# controller_peripherals.net
KiCad netlist of a schematic drawn in Altium Designer
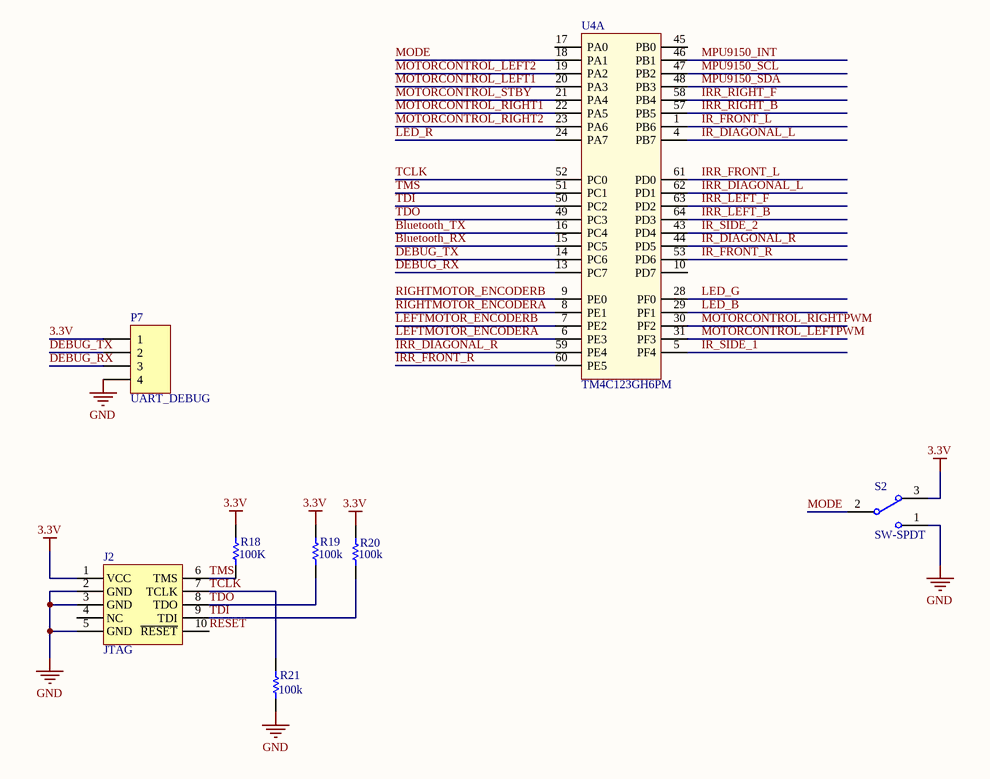
[diagram p0: controller_peripherals.SchDoc]

(export (version "E")
  (design (tool "Eeschema 10.0.6"))
  (components
    (comp (ref "J2")
      (value "JTAG")
      (footprint "HDR2X5")
      (description "10-Pin JTAG Connector for Cortex M4 etc.")
      (libsource (lib "connectors") (part "10-Pin JTAG ARM"))
    )
    (comp (ref "P7")
      (value "UART_DEBUG")
      (footprint "HDR1X4")
      (description "Header, 4-Pin")
      (fields (field (name "PUBLISHER") "Altium Limited"))
      (libsource (lib "Miscellaneous Connectors") (part "Header 4"))
    )
    (comp (ref "R18")
      (value "100K")
      (footprint "0603")
      (description "Resistor")
      (fields (field (name "PUBLISHER") "Altium Limited"))
      (libsource (lib "passives") (part "Resistor"))
    )
    (comp (ref "R19")
      (value "100k")
      (footprint "0603")
      (description "Resistor")
      (fields (field (name "PUBLISHER") "Altium Limited"))
      (libsource (lib "passives") (part "Resistor"))
    )
    (comp (ref "R20")
      (value "100k")
      (footprint "0603")
      (description "Resistor")
      (fields (field (name "PUBLISHER") "Altium Limited"))
      (libsource (lib "passives") (part "Resistor"))
    )
    (comp (ref "R21")
      (value "100k")
      (footprint "0603")
      (description "Resistor")
      (fields (field (name "PUBLISHER") "Altium Limited"))
      (libsource (lib "passives") (part "Resistor"))
    )
    (comp (ref "S2")
      (value "SW-SPDT")
      (footprint "SPDT Switch")
      (description "SPDT Subminiature Toggle Switch, Right Angle Mounting, Vertical Actuation")
      (fields (field (name "PUBLISHER") "Altium Limited"))
      (libsource (lib "switches") (part "SW-SPDT"))
    )
    (comp (ref "U4")
      (value "TM4C123GH6PM")
      (footprint "TSQFP50P1200X1200X145-64N")
      (description "Tiva C TM4C123GH6PM")
      (libsource (lib "microcontrollers") (part "TM4C123GH6PM"))
    )
  )
  (nets
    (net (code "1") (name "/Bluetooth_RX") (class "Default")
      (node (ref "U4") (pin "15") (pinfunction "PC5_15") (pintype "passive"))
    )
    (net (code "2") (name "/Bluetooth_TX") (class "Default")
      (node (ref "U4") (pin "16") (pinfunction "PC4_16") (pintype "passive"))
    )
    (net (code "3") (name "/DEBUG_RX") (class "Default")
      (node (ref "P7") (pin "3") (pinfunction "3_3") (pintype "passive"))
      (node (ref "U4") (pin "13") (pinfunction "PC7_13") (pintype "passive"))
    )
    (net (code "4") (name "/DEBUG_TX") (class "Default")
      (node (ref "P7") (pin "2") (pinfunction "2_2") (pintype "passive"))
      (node (ref "U4") (pin "14") (pinfunction "PC6_14") (pintype "passive"))
    )
    (net (code "5") (name "/IRR_DIAGONAL_L") (class "Default")
      (node (ref "U4") (pin "62") (pinfunction "PD1_62") (pintype "passive"))
    )
    (net (code "6") (name "/IRR_DIAGONAL_R") (class "Default")
      (node (ref "U4") (pin "59") (pinfunction "PE4_59") (pintype "passive"))
    )
    (net (code "7") (name "/IRR_FRONT_L") (class "Default")
      (node (ref "U4") (pin "61") (pinfunction "PD0_61") (pintype "passive"))
    )
    (net (code "8") (name "/IRR_FRONT_R") (class "Default")
      (node (ref "U4") (pin "60") (pinfunction "PE5_60") (pintype "passive"))
    )
    (net (code "9") (name "/IRR_LEFT_B") (class "Default")
      (node (ref "U4") (pin "64") (pinfunction "PD3_64") (pintype "passive"))
    )
    (net (code "10") (name "/IRR_LEFT_F") (class "Default")
      (node (ref "U4") (pin "63") (pinfunction "PD2_63") (pintype "passive"))
    )
    (net (code "11") (name "/IRR_RIGHT_B") (class "Default")
      (node (ref "U4") (pin "57") (pinfunction "PB5_57") (pintype "passive"))
    )
    (net (code "12") (name "/IRR_RIGHT_F") (class "Default")
      (node (ref "U4") (pin "58") (pinfunction "PB4_58") (pintype "passive"))
    )
    (net (code "13") (name "/IR_DIAGONAL_L") (class "Default")
      (node (ref "U4") (pin "4") (pinfunction "PB7_4") (pintype "passive"))
    )
    (net (code "14") (name "/IR_DIAGONAL_R") (class "Default")
      (node (ref "U4") (pin "44") (pinfunction "PD5_44") (pintype "passive"))
    )
    (net (code "15") (name "/IR_FRONT_L") (class "Default")
      (node (ref "U4") (pin "1") (pinfunction "PB6_1") (pintype "passive"))
    )
    (net (code "16") (name "/IR_FRONT_R") (class "Default")
      (node (ref "U4") (pin "53") (pinfunction "PD6_53") (pintype "passive"))
    )
    (net (code "17") (name "/IR_SIDE_1") (class "Default")
      (node (ref "U4") (pin "5") (pinfunction "PF4_5") (pintype "passive"))
    )
    (net (code "18") (name "/IR_SIDE_2") (class "Default")
      (node (ref "U4") (pin "43") (pinfunction "PD4_43") (pintype "passive"))
    )
    (net (code "19") (name "/LED_B") (class "Default")
      (node (ref "U4") (pin "29") (pinfunction "PF1_29") (pintype "passive"))
    )
    (net (code "20") (name "/LED_G") (class "Default")
      (node (ref "U4") (pin "28") (pinfunction "PF0_28") (pintype "passive"))
    )
    (net (code "21") (name "/LED_R") (class "Default")
      (node (ref "U4") (pin "24") (pinfunction "PA7_24") (pintype "passive"))
    )
    (net (code "22") (name "/LEFTMOTOR_ENCODERA") (class "Default")
      (node (ref "U4") (pin "6") (pinfunction "PE3_6") (pintype "passive"))
    )
    (net (code "23") (name "/LEFTMOTOR_ENCODERB") (class "Default")
      (node (ref "U4") (pin "7") (pinfunction "PE2_7") (pintype "passive"))
    )
    (net (code "24") (name "/MODE") (class "Default")
      (node (ref "S2") (pin "2") (pinfunction "2_2") (pintype "passive"))
      (node (ref "U4") (pin "18") (pinfunction "PA1_18") (pintype "passive"))
    )
    (net (code "25") (name "/MOTORCONTROL_LEFT1") (class "Default")
      (node (ref "U4") (pin "20") (pinfunction "PA3_20") (pintype "passive"))
    )
    (net (code "26") (name "/MOTORCONTROL_LEFT2") (class "Default")
      (node (ref "U4") (pin "19") (pinfunction "PA2_19") (pintype "passive"))
    )
    (net (code "27") (name "/MOTORCONTROL_LEFTPWM") (class "Default")
      (node (ref "U4") (pin "31") (pinfunction "PF3_31") (pintype "passive"))
    )
    (net (code "28") (name "/MOTORCONTROL_RIGHT1") (class "Default")
      (node (ref "U4") (pin "22") (pinfunction "PA5_22") (pintype "passive"))
    )
    (net (code "29") (name "/MOTORCONTROL_RIGHT2") (class "Default")
      (node (ref "U4") (pin "23") (pinfunction "PA6_23") (pintype "passive"))
    )
    (net (code "30") (name "/MOTORCONTROL_RIGHTPWM") (class "Default")
      (node (ref "U4") (pin "30") (pinfunction "PF2_30") (pintype "passive"))
    )
    (net (code "31") (name "/MOTORCONTROL_STBY") (class "Default")
      (node (ref "U4") (pin "21") (pinfunction "PA4_21") (pintype "passive"))
    )
    (net (code "32") (name "/MPU9150_INT") (class "Default")
      (node (ref "U4") (pin "46") (pinfunction "PB1_46") (pintype "passive"))
    )
    (net (code "33") (name "/MPU9150_SCL") (class "Default")
      (node (ref "U4") (pin "47") (pinfunction "PB2_47") (pintype "passive"))
    )
    (net (code "34") (name "/MPU9150_SDA") (class "Default")
      (node (ref "U4") (pin "48") (pinfunction "PB3_48") (pintype "passive"))
    )
    (net (code "35") (name "/RESET") (class "Default")
      (node (ref "J2") (pin "10") (pinfunction "~{RESET}_10") (pintype "passive"))
    )
    (net (code "36") (name "/RIGHTMOTOR_ENCODERA") (class "Default")
      (node (ref "U4") (pin "8") (pinfunction "PE1_8") (pintype "passive"))
    )
    (net (code "37") (name "/RIGHTMOTOR_ENCODERB") (class "Default")
      (node (ref "U4") (pin "9") (pinfunction "PE0_9") (pintype "passive"))
    )
    (net (code "38") (name "/TCLK") (class "Default")
      (node (ref "J2") (pin "7") (pinfunction "TCLK_7") (pintype "passive"))
      (node (ref "R21") (pin "2") (pinfunction "2_2") (pintype "passive"))
      (node (ref "U4") (pin "52") (pinfunction "PC0_52") (pintype "passive"))
    )
    (net (code "39") (name "/TDI") (class "Default")
      (node (ref "J2") (pin "9") (pinfunction "TDI_9") (pintype "passive"))
      (node (ref "R20") (pin "1") (pinfunction "1_1") (pintype "passive"))
      (node (ref "U4") (pin "50") (pinfunction "PC2_50") (pintype "passive"))
    )
    (net (code "40") (name "/TDO") (class "Default")
      (node (ref "J2") (pin "8") (pinfunction "TDO_8") (pintype "passive"))
      (node (ref "R19") (pin "1") (pinfunction "1_1") (pintype "passive"))
      (node (ref "U4") (pin "49") (pinfunction "PC3_49") (pintype "passive"))
    )
    (net (code "41") (name "/TMS") (class "Default")
      (node (ref "J2") (pin "6") (pinfunction "TMS_6") (pintype "passive"))
      (node (ref "R18") (pin "1") (pinfunction "1_1") (pintype "passive"))
      (node (ref "U4") (pin "51") (pinfunction "PC1_51") (pintype "passive"))
    )
    (net (code "42") (name "3.3V") (class "Default")
      (node (ref "J2") (pin "1") (pinfunction "VCC_1") (pintype "passive"))
      (node (ref "P7") (pin "1") (pinfunction "1_1") (pintype "passive"))
      (node (ref "R18") (pin "2") (pinfunction "2_2") (pintype "passive"))
      (node (ref "R19") (pin "2") (pinfunction "2_2") (pintype "passive"))
      (node (ref "R20") (pin "2") (pinfunction "2_2") (pintype "passive"))
      (node (ref "S2") (pin "3") (pinfunction "3_3") (pintype "passive"))
    )
    (net (code "43") (name "GND") (class "Default")
      (node (ref "J2") (pin "2") (pinfunction "GND_2") (pintype "passive"))
      (node (ref "J2") (pin "3") (pinfunction "GND_3") (pintype "passive"))
      (node (ref "J2") (pin "5") (pinfunction "GND_5") (pintype "passive"))
      (node (ref "P7") (pin "4") (pinfunction "4_4") (pintype "passive"))
      (node (ref "R21") (pin "1") (pinfunction "1_1") (pintype "passive"))
      (node (ref "S2") (pin "1") (pinfunction "1_1") (pintype "passive"))
    )
    (net (code "44") (name "unconnected-(J2-NC-Pad4)") (class "Default")
      (node (ref "J2") (pin "4") (pinfunction "NC_4") (pintype "passive"))
    )
    (net (code "45") (name "unconnected-(U4A-PA0-Pad17)") (class "Default")
      (node (ref "U4") (pin "17") (pinfunction "PA0_17") (pintype "passive"))
    )
    (net (code "46") (name "unconnected-(U4A-PB0-Pad45)") (class "Default")
      (node (ref "U4") (pin "45") (pinfunction "PB0_45") (pintype "passive"))
    )
    (net (code "47") (name "unconnected-(U4A-PD7-Pad10)") (class "Default")
      (node (ref "U4") (pin "10") (pinfunction "PD7_10") (pintype "passive"))
    )
  )
)
